# chicken-shield.net
KiCad netlist of a schematic drawn in EAGLE
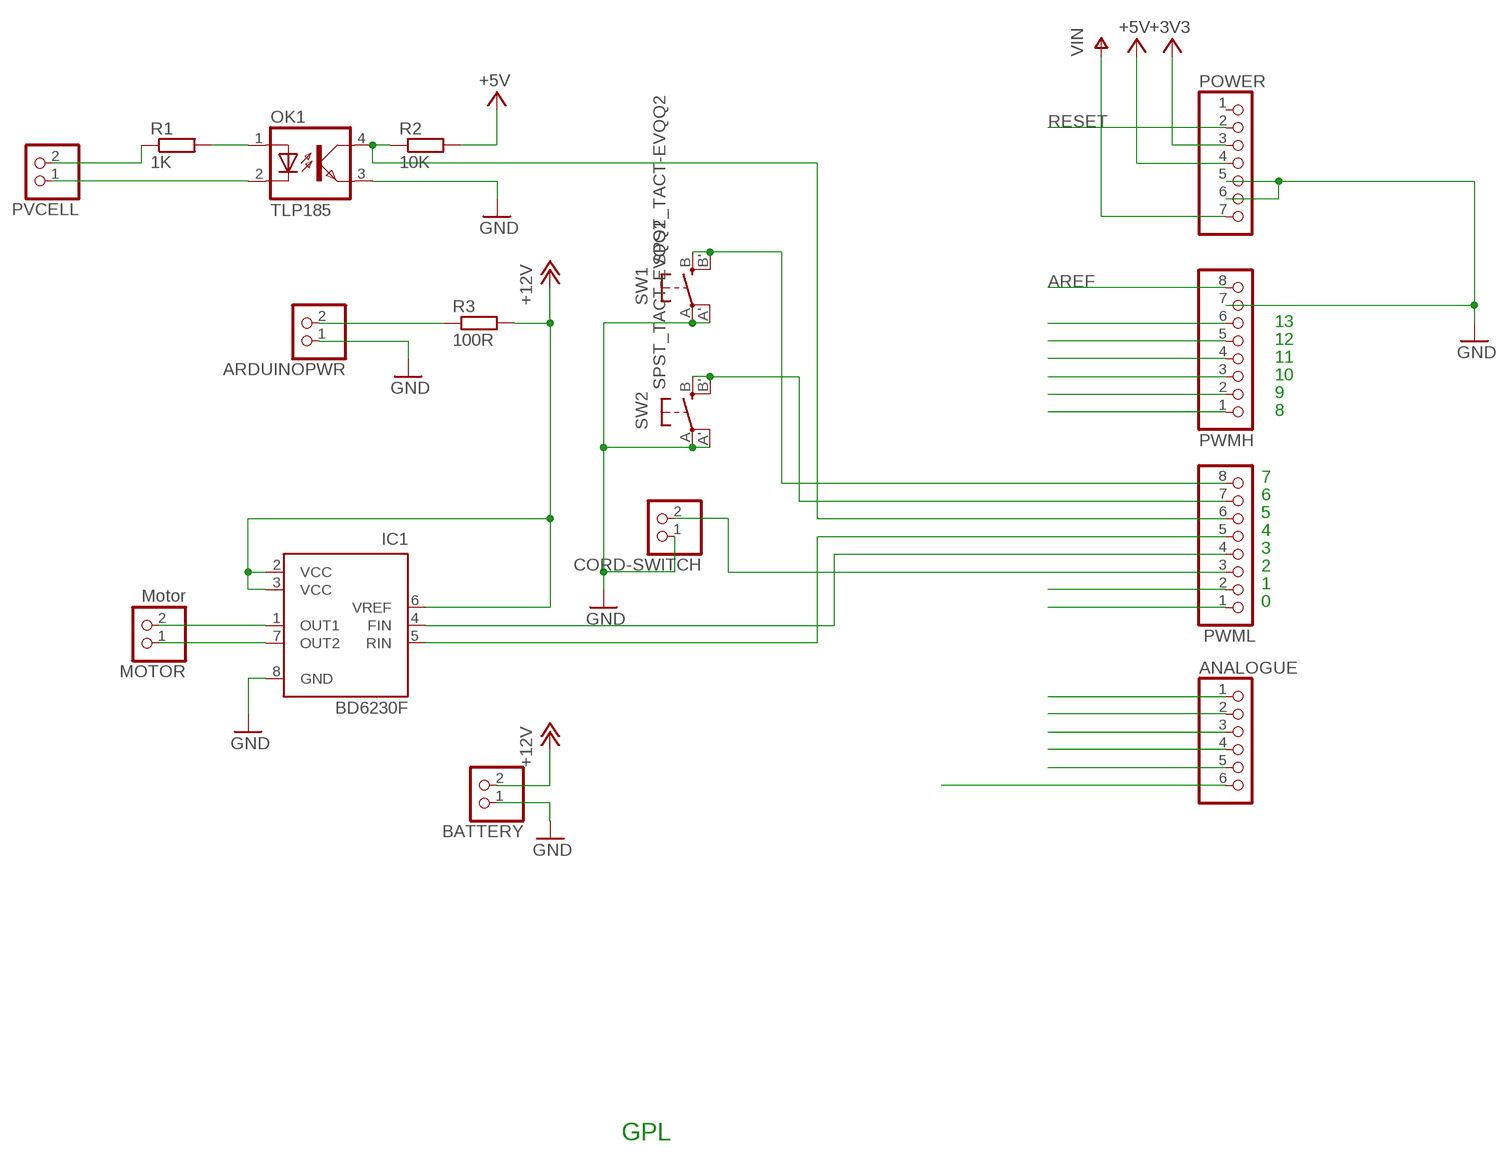
[diagram p0: schematic, sheet 1]

(export (version "E")
  (design (tool "Eeschema 10.0.6"))
  (components
    (comp (ref "ANALOGUE")
      (value "PINHD-1X6")
      (footprint "eagle-import:1X06")
      (libsource (lib "eagle-import") (part "PINHD-1X6"))
    )
    (comp (ref "ARDUINOPWR")
      (value "PINHD-1X2")
      (footprint "eagle-import:1X02")
      (libsource (lib "eagle-import") (part "PINHD-1X2"))
    )
    (comp (ref "BATTERY")
      (value "PINHD-1X2")
      (footprint "eagle-import:1X02")
      (libsource (lib "eagle-import") (part "PINHD-1X2"))
    )
    (comp (ref "CORD-SWITCH")
      (value "PINHD-1X2")
      (footprint "eagle-import:1X02")
      (libsource (lib "eagle-import") (part "PINHD-1X2"))
    )
    (comp (ref "IC1")
      (value "BD6230F")
      (footprint "eagle-import:SOP8")
      (fields (field (name "MPN") "BD6230F-E2"))
      (libsource (lib "eagle-import") (part "BD623F0"))
    )
    (comp (ref "MOTOR")
      (value "Motor")
      (footprint "eagle-import:1X02")
      (libsource (lib "eagle-import") (part "PINHD-1X2"))
    )
    (comp (ref "OK1")
      (value "TLP185")
      (footprint "eagle-import:MINI-FLAT-4")
      (libsource (lib "eagle-import") (part "TLP283"))
    )
    (comp (ref "POWER")
      (value "PINHD-1X7")
      (footprint "eagle-import:1X07")
      (libsource (lib "eagle-import") (part "PINHD-1X7"))
    )
    (comp (ref "PVCELL")
      (value "PINHD-1X2")
      (footprint "eagle-import:1X02")
      (libsource (lib "eagle-import") (part "PINHD-1X2"))
    )
    (comp (ref "PWMH")
      (value "PINHD-1X8")
      (footprint "eagle-import:1X08")
      (libsource (lib "eagle-import") (part "PINHD-1X8"))
    )
    (comp (ref "PWML")
      (value "PINHD-1X8")
      (footprint "eagle-import:1X08")
      (libsource (lib "eagle-import") (part "PINHD-1X8"))
    )
    (comp (ref "R1")
      (value "1K")
      (footprint "eagle-import:M0805")
      (libsource (lib "eagle-import") (part "R-EU_M0805"))
    )
    (comp (ref "R2")
      (value "10K")
      (footprint "eagle-import:M0805")
      (libsource (lib "eagle-import") (part "R-EU_M0805"))
    )
    (comp (ref "R3")
      (value "100R")
      (footprint "eagle-import:0204_7")
      (libsource (lib "eagle-import") (part "R-EU_0204/7"))
    )
    (comp (ref "SW1")
      (value "SPST_TACT-EVQQ2")
      (footprint "eagle-import:EVQ-Q2")
      (libsource (lib "eagle-import") (part "SPST_TACT-EVQQ2"))
    )
    (comp (ref "SW2")
      (value "SPST_TACT-EVQQ2")
      (footprint "eagle-import:EVQ-Q2")
      (libsource (lib "eagle-import") (part "SPST_TACT-EVQQ2"))
    )
  )
  (nets
    (net (code "1") (name "+3V3") (class "Default")
      (node (ref "POWER") (pin "3") (pinfunction "3_3") (pintype "passive"))
    )
    (net (code "2") (name "+5V") (class "Default")
      (node (ref "POWER") (pin "4") (pinfunction "4_4") (pintype "passive"))
      (node (ref "R2") (pin "2") (pinfunction "2_2") (pintype "passive"))
    )
    (net (code "3") (name "+12V") (class "Default")
      (node (ref "BATTERY") (pin "2") (pinfunction "2_2") (pintype "passive"))
      (node (ref "IC1") (pin "2") (pinfunction "VCC_2") (pintype "power_in"))
      (node (ref "IC1") (pin "3") (pinfunction "VCC_3") (pintype "power_in"))
      (node (ref "IC1") (pin "6") (pinfunction "VREF_6") (pintype "passive"))
      (node (ref "R3") (pin "2") (pinfunction "2_2") (pintype "passive"))
    )
    (net (code "4") (name "/AREF") (class "Default")
      (node (ref "PWMH") (pin "8") (pinfunction "8_8") (pintype "passive"))
    )
    (net (code "5") (name "/RESET") (class "Default")
      (node (ref "POWER") (pin "2") (pinfunction "2_2") (pintype "passive"))
    )
    (net (code "6") (name "GND") (class "Default")
      (node (ref "ARDUINOPWR") (pin "1") (pinfunction "1_1") (pintype "passive"))
      (node (ref "BATTERY") (pin "1") (pinfunction "1_1") (pintype "passive"))
      (node (ref "CORD-SWITCH") (pin "1") (pinfunction "1_1") (pintype "passive"))
      (node (ref "IC1") (pin "8") (pinfunction "GND_8") (pintype "power_in"))
      (node (ref "OK1") (pin "3") (pinfunction "EMIT_3") (pintype "passive"))
      (node (ref "POWER") (pin "5") (pinfunction "5_5") (pintype "passive"))
      (node (ref "POWER") (pin "6") (pinfunction "6_6") (pintype "passive"))
      (node (ref "PWMH") (pin "7") (pinfunction "7_7") (pintype "passive"))
      (node (ref "SW1") (pin "A") (pinfunction "P_A") (pintype "passive"))
      (node (ref "SW1") (pin "A'") (pinfunction "P1_A'") (pintype "passive"))
      (node (ref "SW2") (pin "A") (pinfunction "P_A") (pintype "passive"))
      (node (ref "SW2") (pin "A'") (pinfunction "P1_A'") (pintype "passive"))
    )
    (net (code "7") (name "Net-(ARDUINOPWR-Pad2)") (class "Default")
      (node (ref "ARDUINOPWR") (pin "2") (pinfunction "2_2") (pintype "passive"))
      (node (ref "R3") (pin "1") (pinfunction "1_1") (pintype "passive"))
    )
    (net (code "8") (name "Net-(CORD-SWITCH-Pad2)") (class "Default")
      (node (ref "CORD-SWITCH") (pin "2") (pinfunction "2_2") (pintype "passive"))
      (node (ref "PWML") (pin "3") (pinfunction "3_3") (pintype "passive"))
    )
    (net (code "9") (name "Net-(IC1-FIN)") (class "Default")
      (node (ref "IC1") (pin "4") (pinfunction "FIN_4") (pintype "input"))
      (node (ref "PWML") (pin "4") (pinfunction "4_4") (pintype "passive"))
    )
    (net (code "10") (name "Net-(IC1-OUT1)") (class "Default")
      (node (ref "IC1") (pin "1") (pinfunction "OUT1_1") (pintype "output"))
      (node (ref "MOTOR") (pin "2") (pinfunction "2_2") (pintype "passive"))
    )
    (net (code "11") (name "Net-(IC1-OUT2)") (class "Default")
      (node (ref "IC1") (pin "7") (pinfunction "OUT2_7") (pintype "output"))
      (node (ref "MOTOR") (pin "1") (pinfunction "1_1") (pintype "passive"))
    )
    (net (code "12") (name "Net-(IC1-RIN)") (class "Default")
      (node (ref "IC1") (pin "5") (pinfunction "RIN_5") (pintype "input"))
      (node (ref "PWML") (pin "5") (pinfunction "5_5") (pintype "passive"))
    )
    (net (code "13") (name "Net-(OK1-A)") (class "Default")
      (node (ref "OK1") (pin "1") (pinfunction "A_1") (pintype "passive"))
      (node (ref "R1") (pin "2") (pinfunction "2_2") (pintype "passive"))
    )
    (net (code "14") (name "Net-(OK1-C)") (class "Default")
      (node (ref "OK1") (pin "2") (pinfunction "C_2") (pintype "passive"))
      (node (ref "PVCELL") (pin "1") (pinfunction "1_1") (pintype "passive"))
    )
    (net (code "15") (name "Net-(OK1-COL)") (class "Default")
      (node (ref "OK1") (pin "4") (pinfunction "COL_4") (pintype "passive"))
      (node (ref "PWML") (pin "6") (pinfunction "6_6") (pintype "passive"))
      (node (ref "R2") (pin "1") (pinfunction "1_1") (pintype "passive"))
    )
    (net (code "16") (name "Net-(PVCELL-Pad2)") (class "Default")
      (node (ref "PVCELL") (pin "2") (pinfunction "2_2") (pintype "passive"))
      (node (ref "R1") (pin "1") (pinfunction "1_1") (pintype "passive"))
    )
    (net (code "17") (name "Net-(SW1-S)") (class "Default")
      (node (ref "PWML") (pin "8") (pinfunction "8_8") (pintype "passive"))
      (node (ref "SW1") (pin "B") (pinfunction "S_B") (pintype "passive"))
      (node (ref "SW1") (pin "B'") (pinfunction "S1_B'") (pintype "passive"))
    )
    (net (code "18") (name "Net-(SW2-S)") (class "Default")
      (node (ref "PWML") (pin "7") (pinfunction "7_7") (pintype "passive"))
      (node (ref "SW2") (pin "B") (pinfunction "S_B") (pintype "passive"))
      (node (ref "SW2") (pin "B'") (pinfunction "S1_B'") (pintype "passive"))
    )
    (net (code "19") (name "VIN") (class "Default")
      (node (ref "POWER") (pin "7") (pinfunction "7_7") (pintype "passive"))
    )
    (net (code "20") (name "unconnected-(ANALOGUE-Pad1)") (class "Default")
      (node (ref "ANALOGUE") (pin "1") (pinfunction "1_1") (pintype "passive"))
    )
    (net (code "21") (name "unconnected-(ANALOGUE-Pad2)") (class "Default")
      (node (ref "ANALOGUE") (pin "2") (pinfunction "2_2") (pintype "passive"))
    )
    (net (code "22") (name "unconnected-(ANALOGUE-Pad3)") (class "Default")
      (node (ref "ANALOGUE") (pin "3") (pinfunction "3_3") (pintype "passive"))
    )
    (net (code "23") (name "unconnected-(ANALOGUE-Pad4)") (class "Default")
      (node (ref "ANALOGUE") (pin "4") (pinfunction "4_4") (pintype "passive"))
    )
    (net (code "24") (name "unconnected-(ANALOGUE-Pad5)") (class "Default")
      (node (ref "ANALOGUE") (pin "5") (pinfunction "5_5") (pintype "passive"))
    )
    (net (code "25") (name "unconnected-(ANALOGUE-Pad6)") (class "Default")
      (node (ref "ANALOGUE") (pin "6") (pinfunction "6_6") (pintype "passive"))
    )
    (net (code "26") (name "unconnected-(POWER-Pad1)") (class "Default")
      (node (ref "POWER") (pin "1") (pinfunction "1_1") (pintype "passive"))
    )
    (net (code "27") (name "unconnected-(PWMH-Pad1)") (class "Default")
      (node (ref "PWMH") (pin "1") (pinfunction "1_1") (pintype "passive"))
    )
    (net (code "28") (name "unconnected-(PWMH-Pad2)") (class "Default")
      (node (ref "PWMH") (pin "2") (pinfunction "2_2") (pintype "passive"))
    )
    (net (code "29") (name "unconnected-(PWMH-Pad3)") (class "Default")
      (node (ref "PWMH") (pin "3") (pinfunction "3_3") (pintype "passive"))
    )
    (net (code "30") (name "unconnected-(PWMH-Pad4)") (class "Default")
      (node (ref "PWMH") (pin "4") (pinfunction "4_4") (pintype "passive"))
    )
    (net (code "31") (name "unconnected-(PWMH-Pad5)") (class "Default")
      (node (ref "PWMH") (pin "5") (pinfunction "5_5") (pintype "passive"))
    )
    (net (code "32") (name "unconnected-(PWMH-Pad6)") (class "Default")
      (node (ref "PWMH") (pin "6") (pinfunction "6_6") (pintype "passive"))
    )
    (net (code "33") (name "unconnected-(PWML-Pad1)") (class "Default")
      (node (ref "PWML") (pin "1") (pinfunction "1_1") (pintype "passive"))
    )
    (net (code "34") (name "unconnected-(PWML-Pad2)") (class "Default")
      (node (ref "PWML") (pin "2") (pinfunction "2_2") (pintype "passive"))
    )
  )
)
